# OneLedBlinkerWith100kPot.net
KiCad netlist of a schematic drawn in EAGLE
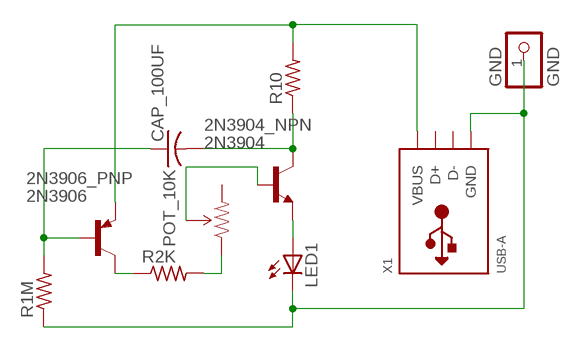
[diagram p0: schematic, sheet 1]

(export (version "E")
  (design (tool "Eeschema 10.0.6"))
  (components
    (comp (ref "2N3904_NPN")
      (value "2N3904")
      (footprint "eagle-import:TO92")
      (libsource (lib "eagle-import") (part "2N3904"))
    )
    (comp (ref "2N3906_PNP")
      (value "2N3906")
      (footprint "eagle-import:TO92")
      (libsource (lib "eagle-import") (part "2N3906"))
    )
    (comp (ref "CAP_100UF")
      (value "C-US025-030X050")
      (footprint "eagle-import:C025-030X050")
      (libsource (lib "eagle-import") (part "C-US025-030X050"))
    )
    (comp (ref "GND")
      (value "GND")
      (footprint "eagle-import:1X01")
      (libsource (lib "eagle-import") (part "PINHD-1X1"))
    )
    (comp (ref "LED1")
      (value "LED5MM")
      (footprint "eagle-import:LED5MM")
      (libsource (lib "eagle-import") (part "LED5MM"))
    )
    (comp (ref "POT_10K")
      (value "TRIMPOTPTH")
      (footprint "eagle-import:TRIM_POT_PTH")
      (libsource (lib "eagle-import") (part "TRIMPOTPTH"))
    )
    (comp (ref "R1M")
      (value "R-US_0207/10")
      (footprint "eagle-import:0207_10")
      (libsource (lib "eagle-import") (part "R-US_0207/10"))
    )
    (comp (ref "R2K")
      (value "R-US_0207/10")
      (footprint "eagle-import:0207_10")
      (libsource (lib "eagle-import") (part "R-US_0207/10"))
    )
    (comp (ref "R10")
      (value "R-US_0207/10")
      (footprint "eagle-import:0207_10")
      (libsource (lib "eagle-import") (part "R-US_0207/10"))
    )
    (comp (ref "X1")
      (value "USB-A")
      (footprint "eagle-import:MOLEX_480371000")
      (libsource (lib "eagle-import") (part "USB-A"))
    )
  )
  (nets
    (net (code "1") (name "Net-(2N3904_NPN-B)") (class "Default")
      (node (ref "2N3904_NPN") (pin "2") (pinfunction "B_2") (pintype "passive"))
      (node (ref "POT_10K") (pin "2") (pinfunction "WIPER_2") (pintype "passive"))
    )
    (net (code "2") (name "Net-(2N3904_NPN-C)") (class "Default")
      (node (ref "2N3904_NPN") (pin "1") (pinfunction "C_1") (pintype "passive"))
      (node (ref "CAP_100UF") (pin "2") (pinfunction "2_2") (pintype "passive"))
      (node (ref "R10") (pin "1") (pinfunction "1_1") (pintype "passive"))
    )
    (net (code "3") (name "Net-(2N3904_NPN-E)") (class "Default")
      (node (ref "2N3904_NPN") (pin "3") (pinfunction "E_3") (pintype "passive"))
      (node (ref "LED1") (pin "A") (pinfunction "A_A") (pintype "passive"))
    )
    (net (code "4") (name "Net-(2N3906_PNP-B)") (class "Default")
      (node (ref "2N3906_PNP") (pin "2") (pinfunction "B_2") (pintype "passive"))
      (node (ref "CAP_100UF") (pin "1") (pinfunction "1_1") (pintype "passive"))
      (node (ref "R1M") (pin "2") (pinfunction "2_2") (pintype "passive"))
    )
    (net (code "5") (name "Net-(2N3906_PNP-C)") (class "Default")
      (node (ref "2N3906_PNP") (pin "1") (pinfunction "C_1") (pintype "passive"))
      (node (ref "R2K") (pin "1") (pinfunction "1_1") (pintype "passive"))
    )
    (net (code "6") (name "Net-(2N3906_PNP-E)") (class "Default")
      (node (ref "2N3906_PNP") (pin "3") (pinfunction "E_3") (pintype "passive"))
      (node (ref "R10") (pin "2") (pinfunction "2_2") (pintype "passive"))
      (node (ref "X1") (pin "1") (pinfunction "VBUS_1") (pintype "power_in"))
    )
    (net (code "7") (name "Net-(LED1-C)") (class "Default")
      (node (ref "GND") (pin "1") (pinfunction "1_1") (pintype "passive"))
      (node (ref "LED1") (pin "K") (pinfunction "C_K") (pintype "passive"))
      (node (ref "R1M") (pin "1") (pinfunction "1_1") (pintype "passive"))
      (node (ref "X1") (pin "4") (pinfunction "GND_4") (pintype "power_in"))
    )
    (net (code "8") (name "Net-(POT_10K-CCW)") (class "Default")
      (node (ref "POT_10K") (pin "1") (pinfunction "CCW_1") (pintype "passive"))
      (node (ref "R2K") (pin "2") (pinfunction "2_2") (pintype "passive"))
    )
    (net (code "9") (name "unconnected-(POT_10K-CW-Pad3)") (class "Default")
      (node (ref "POT_10K") (pin "3") (pinfunction "CW_3") (pintype "passive"))
    )
    (net (code "10") (name "unconnected-(X1-D+-Pad3)") (class "Default")
      (node (ref "X1") (pin "3") (pinfunction "D+_3") (pintype "bidirectional"))
    )
    (net (code "11") (name "unconnected-(X1-D--Pad2)") (class "Default")
      (node (ref "X1") (pin "2") (pinfunction "D-_2") (pintype "bidirectional"))
    )
  )
)
